# HT66F0185_NightLED_V4_0.net
KiCad netlist of a schematic drawn in Altium Designer
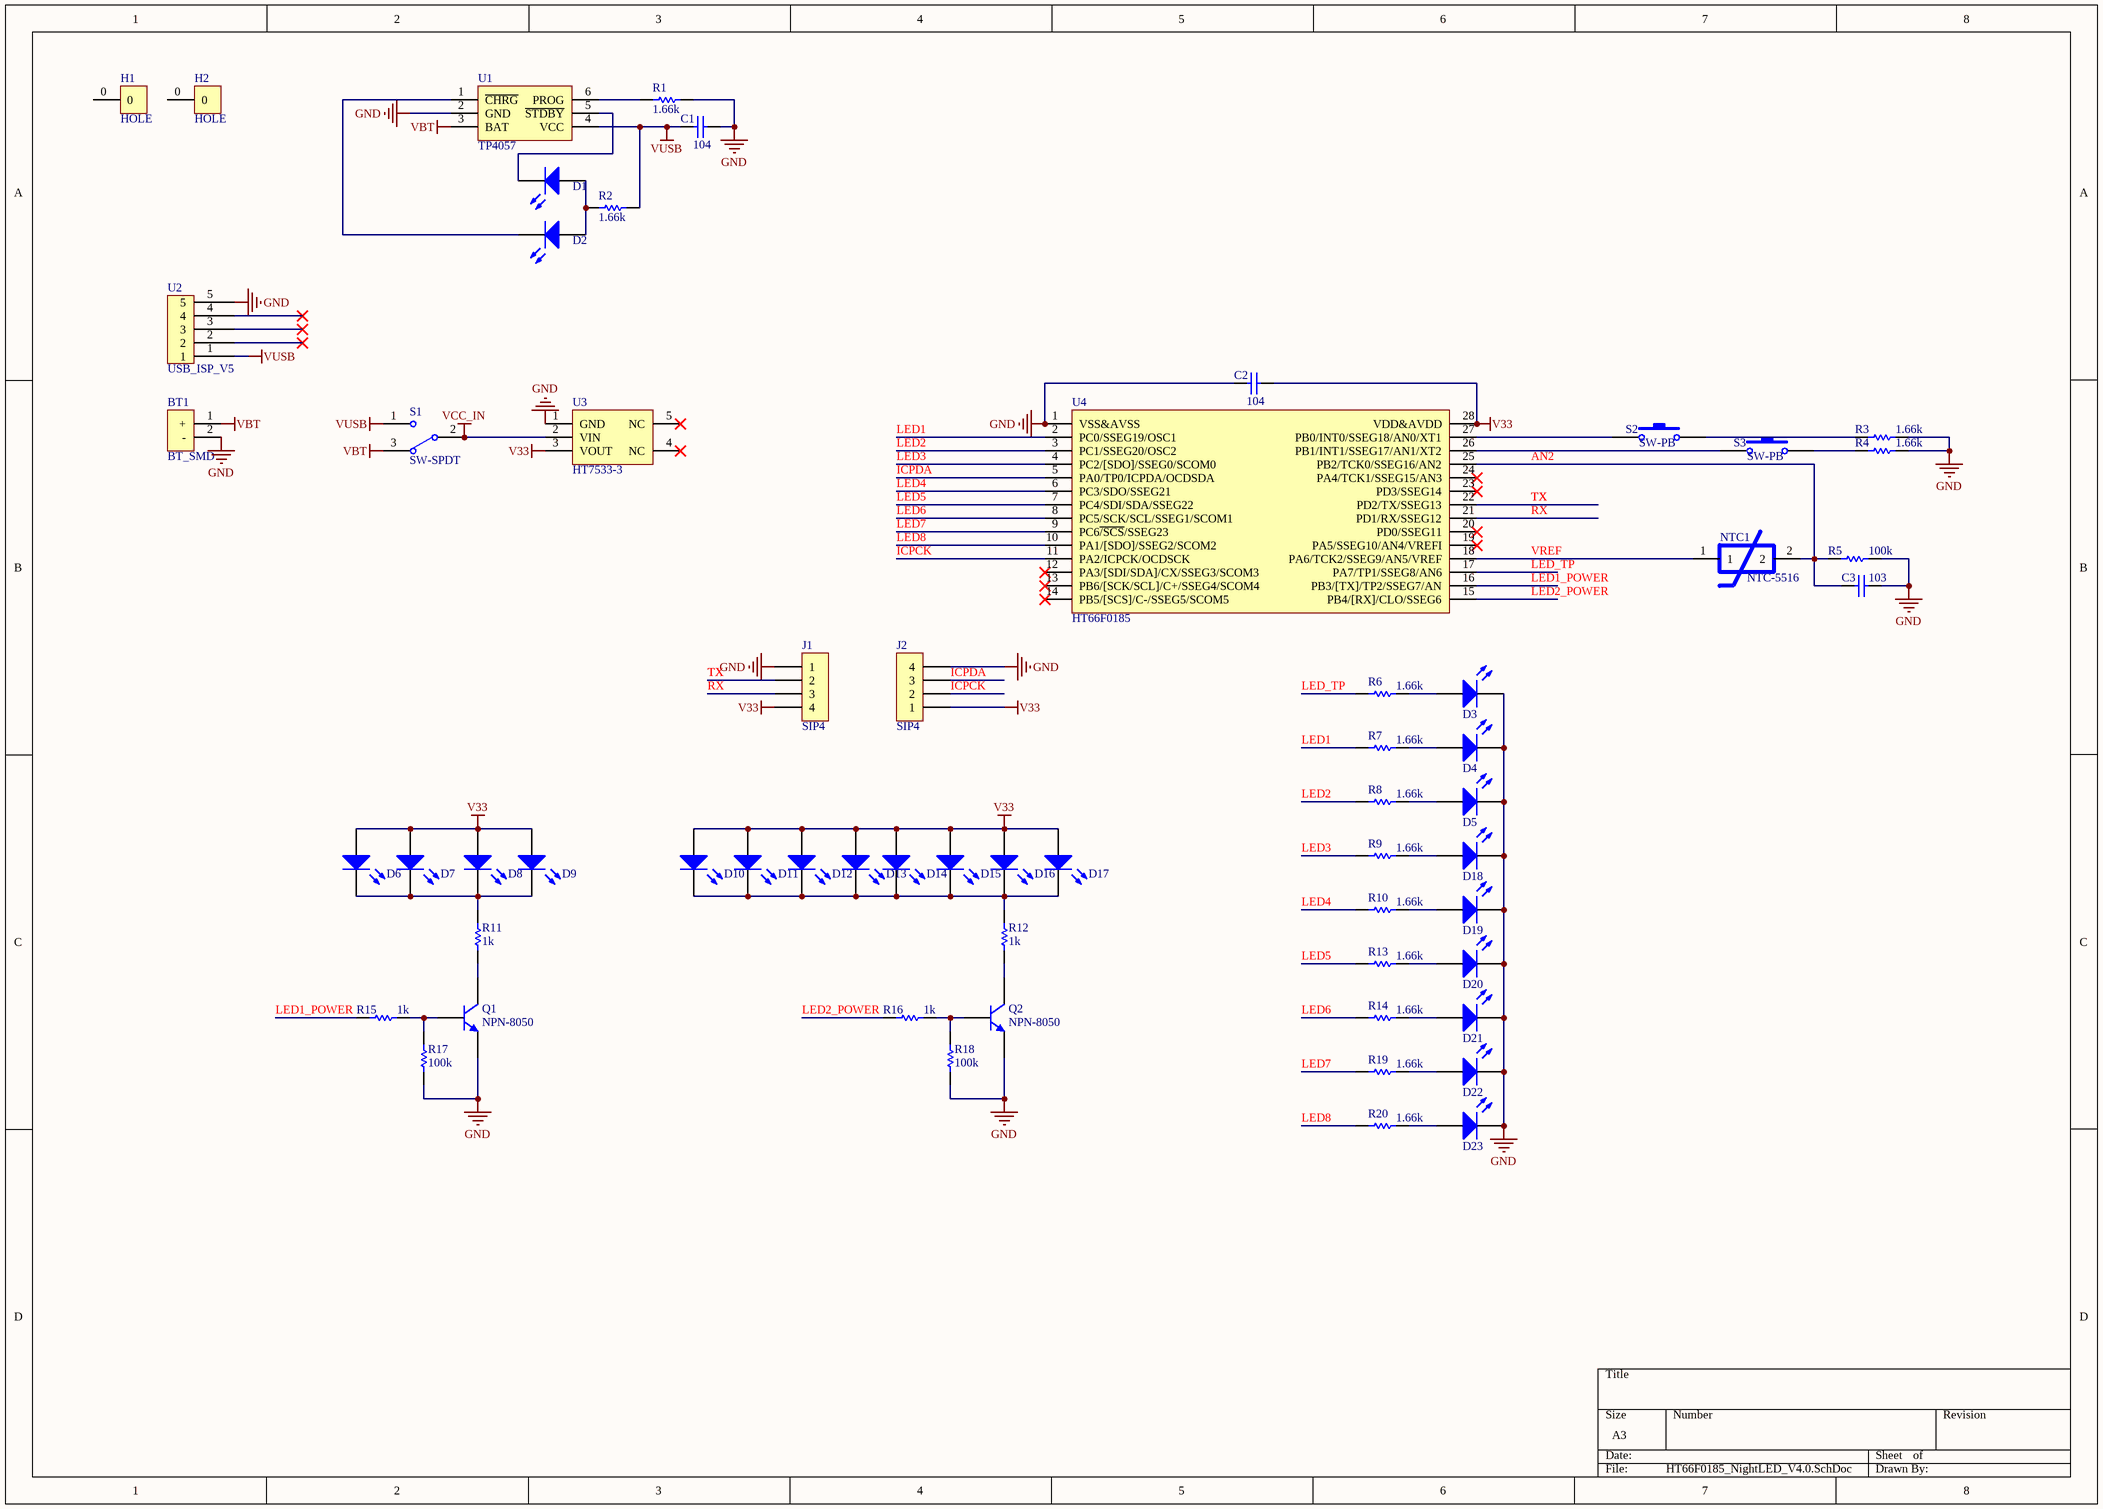
[diagram p0: HT66F0185_NightLED_V4.0.SchDoc]

(export (version "E")
  (design (tool "Eeschema 10.0.6"))
  (components
    (comp (ref "BT1")
      (value "BT_SMD")
      (footprint "PIN_2")
      (libsource (lib "HT66F0185_NightLED") (part "BT_SMD"))
    )
    (comp (ref "C1")
      (value "104")
      (footprint "C_0603")
      (description "Capacitor")
      (fields (field (name "Comment") "Cap") (field (name "PUBLISHER") "Altium Limited"))
      (libsource (lib "Miscellaneous Devices") (part "Cap"))
    )
    (comp (ref "C2")
      (value "104")
      (footprint "C_0603")
      (description "Capacitor")
      (fields (field (name "Comment") "Cap") (field (name "PUBLISHER") "Altium Limited"))
      (libsource (lib "Miscellaneous Devices") (part "Cap"))
    )
    (comp (ref "C3")
      (value "103")
      (footprint "C_0603")
      (description "Capacitor")
      (fields (field (name "Comment") "Cap") (field (name "PUBLISHER") "Altium Limited"))
      (libsource (lib "Miscellaneous Devices") (part "Cap"))
    )
    (comp (ref "D1")
      (value "LED0")
      (footprint "LED_0805(Y)")
      (description "Typical INFRARED GaAs LED")
      (fields (field (name "PUBLISHER") "Altium Limited"))
      (libsource (lib "zhiwu_Project") (part "LED0"))
    )
    (comp (ref "D2")
      (value "LED0")
      (footprint "LED_0805(Y)")
      (description "Typical INFRARED GaAs LED")
      (fields (field (name "PUBLISHER") "Altium Limited"))
      (libsource (lib "zhiwu_Project") (part "LED0"))
    )
    (comp (ref "D3")
      (value "LED0")
      (footprint "LED_0805(Y)")
      (description "Typical INFRARED GaAs LED")
      (fields (field (name "PUBLISHER") "Altium Limited"))
      (libsource (lib "zhiwu_Project") (part "LED0"))
    )
    (comp (ref "D4")
      (value "LED0")
      (footprint "LED_0805(Y)")
      (description "Typical INFRARED GaAs LED")
      (fields (field (name "PUBLISHER") "Altium Limited"))
      (libsource (lib "zhiwu_Project") (part "LED0"))
    )
    (comp (ref "D5")
      (value "LED0")
      (footprint "LED_0805(Y)")
      (description "Typical INFRARED GaAs LED")
      (fields (field (name "PUBLISHER") "Altium Limited"))
      (libsource (lib "zhiwu_Project") (part "LED0"))
    )
    (comp (ref "D6")
      (value "LED0")
      (footprint "LED_0805(Y)")
      (description "Typical INFRARED GaAs LED")
      (fields (field (name "PUBLISHER") "Altium Limited"))
      (libsource (lib "zhiwu_Project") (part "LED0"))
    )
    (comp (ref "D7")
      (value "LED0")
      (footprint "LED_0805(Y)")
      (description "Typical INFRARED GaAs LED")
      (fields (field (name "PUBLISHER") "Altium Limited"))
      (libsource (lib "zhiwu_Project") (part "LED0"))
    )
    (comp (ref "D8")
      (value "LED0")
      (footprint "LED_0805(Y)")
      (description "Typical INFRARED GaAs LED")
      (fields (field (name "PUBLISHER") "Altium Limited"))
      (libsource (lib "zhiwu_Project") (part "LED0"))
    )
    (comp (ref "D9")
      (value "LED0")
      (footprint "LED_0805(Y)")
      (description "Typical INFRARED GaAs LED")
      (fields (field (name "PUBLISHER") "Altium Limited"))
      (libsource (lib "zhiwu_Project") (part "LED0"))
    )
    (comp (ref "D10")
      (value "LED0")
      (footprint "LED_0805(Y)")
      (description "Typical INFRARED GaAs LED")
      (fields (field (name "PUBLISHER") "Altium Limited"))
      (libsource (lib "zhiwu_Project") (part "LED0"))
    )
    (comp (ref "D11")
      (value "LED0")
      (footprint "LED_0805(Y)")
      (description "Typical INFRARED GaAs LED")
      (fields (field (name "PUBLISHER") "Altium Limited"))
      (libsource (lib "zhiwu_Project") (part "LED0"))
    )
    (comp (ref "D12")
      (value "LED0")
      (footprint "LED_0805(Y)")
      (description "Typical INFRARED GaAs LED")
      (fields (field (name "PUBLISHER") "Altium Limited"))
      (libsource (lib "zhiwu_Project") (part "LED0"))
    )
    (comp (ref "D13")
      (value "LED0")
      (footprint "LED_0805(Y)")
      (description "Typical INFRARED GaAs LED")
      (fields (field (name "PUBLISHER") "Altium Limited"))
      (libsource (lib "zhiwu_Project") (part "LED0"))
    )
    (comp (ref "D14")
      (value "LED0")
      (footprint "LED_0805(Y)")
      (description "Typical INFRARED GaAs LED")
      (fields (field (name "PUBLISHER") "Altium Limited"))
      (libsource (lib "zhiwu_Project") (part "LED0"))
    )
    (comp (ref "D15")
      (value "LED0")
      (footprint "LED_0805(Y)")
      (description "Typical INFRARED GaAs LED")
      (fields (field (name "PUBLISHER") "Altium Limited"))
      (libsource (lib "zhiwu_Project") (part "LED0"))
    )
    (comp (ref "D16")
      (value "LED0")
      (footprint "LED_0805(Y)")
      (description "Typical INFRARED GaAs LED")
      (fields (field (name "PUBLISHER") "Altium Limited"))
      (libsource (lib "zhiwu_Project") (part "LED0"))
    )
    (comp (ref "D17")
      (value "LED0")
      (footprint "LED_0805(Y)")
      (description "Typical INFRARED GaAs LED")
      (fields (field (name "PUBLISHER") "Altium Limited"))
      (libsource (lib "zhiwu_Project") (part "LED0"))
    )
    (comp (ref "D18")
      (value "LED0")
      (footprint "LED_0805(Y)")
      (description "Typical INFRARED GaAs LED")
      (fields (field (name "PUBLISHER") "Altium Limited"))
      (libsource (lib "zhiwu_Project") (part "LED0"))
    )
    (comp (ref "D19")
      (value "LED0")
      (footprint "LED_0805(Y)")
      (description "Typical INFRARED GaAs LED")
      (fields (field (name "PUBLISHER") "Altium Limited"))
      (libsource (lib "zhiwu_Project") (part "LED0"))
    )
    (comp (ref "D20")
      (value "LED0")
      (footprint "LED_0805(Y)")
      (description "Typical INFRARED GaAs LED")
      (fields (field (name "PUBLISHER") "Altium Limited"))
      (libsource (lib "zhiwu_Project") (part "LED0"))
    )
    (comp (ref "D21")
      (value "LED0")
      (footprint "LED_0805(Y)")
      (description "Typical INFRARED GaAs LED")
      (fields (field (name "PUBLISHER") "Altium Limited"))
      (libsource (lib "zhiwu_Project") (part "LED0"))
    )
    (comp (ref "D22")
      (value "LED0")
      (footprint "LED_0805(Y)")
      (description "Typical INFRARED GaAs LED")
      (fields (field (name "PUBLISHER") "Altium Limited"))
      (libsource (lib "zhiwu_Project") (part "LED0"))
    )
    (comp (ref "D23")
      (value "LED0")
      (footprint "LED_0805(Y)")
      (description "Typical INFRARED GaAs LED")
      (fields (field (name "PUBLISHER") "Altium Limited"))
      (libsource (lib "zhiwu_Project") (part "LED0"))
    )
    (comp (ref "H1")
      (value "HOLE")
      (footprint "Screw Hole_NightLED_V4.0")
      (libsource (lib "HT68F001_LED") (part "HOLE"))
    )
    (comp (ref "H2")
      (value "HOLE")
      (footprint "Screw Hole_NightLED_V4.0")
      (libsource (lib "HT68F001_LED") (part "HOLE"))
    )
    (comp (ref "J1")
      (value "SIP4")
      (footprint "PIN_4(SMD) - duplicate")
      (description "jointbar")
      (libsource (lib "接口与插座") (part "SIP4"))
    )
    (comp (ref "J2")
      (value "SIP4")
      (footprint "PIN_4(SMD) - duplicate")
      (description "jointbar")
      (libsource (lib "") (part "SIP4_1"))
    )
    (comp (ref "NTC1")
      (value "NTC-5516")
      (footprint "PIN_2")
      (description "NTC")
      (libsource (lib "HT66F0185_NightLED") (part "NTC"))
    )
    (comp (ref "Q1")
      (value "NPN-8050")
      (footprint "SOT_23_3")
      (description "NPN Bipolar Transistor")
      (fields (field (name "PUBLISHER") "Altium Limited"))
      (libsource (lib "Miscellaneous Devices") (part "NPN"))
    )
    (comp (ref "Q2")
      (value "NPN-8050")
      (footprint "SOT_23_3")
      (description "NPN Bipolar Transistor")
      (fields (field (name "PUBLISHER") "Altium Limited"))
      (libsource (lib "Miscellaneous Devices") (part "NPN"))
    )
    (comp (ref "R1")
      (value "1.66k")
      (footprint "R_0603")
      (description "Resistor")
      (fields (field (name "Comment") "Res1") (field (name "PUBLISHER") "Altium Limited"))
      (libsource (lib "Miscellaneous Devices") (part "Res1"))
    )
    (comp (ref "R2")
      (value "1.66k")
      (footprint "R_0603")
      (description "Resistor")
      (fields (field (name "Comment") "Res1") (field (name "PUBLISHER") "Altium Limited"))
      (libsource (lib "Miscellaneous Devices") (part "Res1"))
    )
    (comp (ref "R3")
      (value "1.66k")
      (footprint "R_0603")
      (description "Resistor")
      (fields (field (name "Comment") "Res1") (field (name "PUBLISHER") "Altium Limited"))
      (libsource (lib "Miscellaneous Devices") (part "Res1"))
    )
    (comp (ref "R4")
      (value "1.66k")
      (footprint "R_0603")
      (description "Resistor")
      (fields (field (name "Comment") "Res1") (field (name "PUBLISHER") "Altium Limited"))
      (libsource (lib "Miscellaneous Devices") (part "Res1"))
    )
    (comp (ref "R5")
      (value "100k")
      (footprint "R_0603")
      (description "Resistor")
      (fields (field (name "Comment") "Res1") (field (name "PUBLISHER") "Altium Limited"))
      (libsource (lib "Miscellaneous Devices") (part "Res1"))
    )
    (comp (ref "R6")
      (value "1.66k")
      (footprint "R_0603")
      (description "Resistor")
      (fields (field (name "Comment") "Res1") (field (name "PUBLISHER") "Altium Limited"))
      (libsource (lib "Miscellaneous Devices") (part "Res1"))
    )
    (comp (ref "R7")
      (value "1.66k")
      (footprint "R_0603")
      (description "Resistor")
      (fields (field (name "Comment") "Res1") (field (name "PUBLISHER") "Altium Limited"))
      (libsource (lib "Miscellaneous Devices") (part "Res1"))
    )
    (comp (ref "R8")
      (value "1.66k")
      (footprint "R_0603")
      (description "Resistor")
      (fields (field (name "Comment") "Res1") (field (name "PUBLISHER") "Altium Limited"))
      (libsource (lib "Miscellaneous Devices") (part "Res1"))
    )
    (comp (ref "R9")
      (value "1.66k")
      (footprint "R_0603")
      (description "Resistor")
      (fields (field (name "Comment") "Res1") (field (name "PUBLISHER") "Altium Limited"))
      (libsource (lib "Miscellaneous Devices") (part "Res1"))
    )
    (comp (ref "R10")
      (value "1.66k")
      (footprint "R_0603")
      (description "Resistor")
      (fields (field (name "Comment") "Res1") (field (name "PUBLISHER") "Altium Limited"))
      (libsource (lib "Miscellaneous Devices") (part "Res1"))
    )
    (comp (ref "R11")
      (value "1k")
      (footprint "R_0603")
      (description "Resistor")
      (fields (field (name "Comment") "Res1") (field (name "PUBLISHER") "Altium Limited"))
      (libsource (lib "Miscellaneous Devices") (part "Res1"))
    )
    (comp (ref "R12")
      (value "1k")
      (footprint "R_0603")
      (description "Resistor")
      (fields (field (name "Comment") "Res1") (field (name "PUBLISHER") "Altium Limited"))
      (libsource (lib "Miscellaneous Devices") (part "Res1"))
    )
    (comp (ref "R13")
      (value "1.66k")
      (footprint "R_0603")
      (description "Resistor")
      (fields (field (name "Comment") "Res1") (field (name "PUBLISHER") "Altium Limited"))
      (libsource (lib "Miscellaneous Devices") (part "Res1"))
    )
    (comp (ref "R14")
      (value "1.66k")
      (footprint "R_0603")
      (description "Resistor")
      (fields (field (name "Comment") "Res1") (field (name "PUBLISHER") "Altium Limited"))
      (libsource (lib "Miscellaneous Devices") (part "Res1"))
    )
    (comp (ref "R15")
      (value "1k")
      (footprint "R_0603")
      (description "Resistor")
      (fields (field (name "Comment") "Res1") (field (name "PUBLISHER") "Altium Limited"))
      (libsource (lib "Miscellaneous Devices") (part "Res1"))
    )
    (comp (ref "R16")
      (value "1k")
      (footprint "R_0603")
      (description "Resistor")
      (fields (field (name "Comment") "Res1") (field (name "PUBLISHER") "Altium Limited"))
      (libsource (lib "Miscellaneous Devices") (part "Res1"))
    )
    (comp (ref "R17")
      (value "100k")
      (footprint "R_0603")
      (description "Resistor")
      (fields (field (name "Comment") "Res1") (field (name "PUBLISHER") "Altium Limited"))
      (libsource (lib "Miscellaneous Devices") (part "Res1"))
    )
    (comp (ref "R18")
      (value "100k")
      (footprint "R_0603")
      (description "Resistor")
      (fields (field (name "Comment") "Res1") (field (name "PUBLISHER") "Altium Limited"))
      (libsource (lib "Miscellaneous Devices") (part "Res1"))
    )
    (comp (ref "R19")
      (value "1.66k")
      (footprint "R_0603")
      (description "Resistor")
      (fields (field (name "Comment") "Res1") (field (name "PUBLISHER") "Altium Limited"))
      (libsource (lib "Miscellaneous Devices") (part "Res1"))
    )
    (comp (ref "R20")
      (value "1.66k")
      (footprint "R_0603")
      (description "Resistor")
      (fields (field (name "Comment") "Res1") (field (name "PUBLISHER") "Altium Limited"))
      (libsource (lib "Miscellaneous Devices") (part "Res1"))
    )
    (comp (ref "S1")
      (value "SW-SPDT")
      (footprint "SW-SPDT")
      (description "SPDT Subminiature Toggle Switch, Right Angle Mounting, Vertical Actuation")
      (fields (field (name "PUBLISHER") "Altium Limited"))
      (libsource (lib "Miscellaneous Devices") (part "SW-SPDT"))
    )
    (comp (ref "S2")
      (value "SW-PB")
      (footprint "micro button_4_SMD")
      (description "Switch")
      (fields (field (name "PUBLISHER") "Altium Limited"))
      (libsource (lib "Miscellaneous Devices") (part "SW-PB"))
    )
    (comp (ref "S3")
      (value "SW-PB")
      (footprint "micro button_2_SMD")
      (description "Switch")
      (fields (field (name "PUBLISHER") "Altium Limited"))
      (libsource (lib "Miscellaneous Devices") (part "SW-PB"))
    )
    (comp (ref "U1")
      (value "TP4057")
      (footprint "SOT_23_6")
      (libsource (lib "HT66F0185_NightLED") (part "TP4057"))
    )
    (comp (ref "U2")
      (value "USB_ISP_V5")
      (footprint "MicroUSB")
      (description "USB")
      (libsource (lib "zhiwu_Project") (part "JP5"))
    )
    (comp (ref "U3")
      (value "HT7533-3")
      (footprint "SOT_23_5")
      (libsource (lib "HT66F0185_NightLED") (part "HT7533-3"))
    )
    (comp (ref "U4")
      (value "HT66F0185")
      (footprint "SSOP_28")
      (libsource (lib "HT66F0185_NightLED") (part "HT66F0185"))
    )
  )
  (nets
    (net (code "1") (name "/AN2") (class "Default")
      (node (ref "C3") (pin "2") (pinfunction "2_2") (pintype "passive"))
      (node (ref "NTC1") (pin "2") (pinfunction "2_2") (pintype "passive"))
      (node (ref "R5") (pin "2") (pinfunction "2_2") (pintype "passive"))
      (node (ref "U4") (pin "25") (pinfunction "PB2/TCK0/SSEG16/AN2_25") (pintype "passive"))
    )
    (net (code "2") (name "/ICPCK") (class "Default")
      (node (ref "J2") (pin "2") (pinfunction "2_2") (pintype "passive"))
      (node (ref "U4") (pin "11") (pinfunction "PA2/ICPCK/OCDSCK_11") (pintype "passive"))
    )
    (net (code "3") (name "/ICPDA") (class "Default")
      (node (ref "J2") (pin "3") (pinfunction "3_3") (pintype "passive"))
      (node (ref "U4") (pin "5") (pinfunction "PA0/TP0/ICPDA/OCDSDA_5") (pintype "passive"))
    )
    (net (code "4") (name "/LED1") (class "Default")
      (node (ref "R7") (pin "2") (pinfunction "2_2") (pintype "passive"))
      (node (ref "U4") (pin "2") (pinfunction "PC0/SSEG19/OSC1_2") (pintype "passive"))
    )
    (net (code "5") (name "/LED1_POWER") (class "Default")
      (node (ref "R15") (pin "2") (pinfunction "2_2") (pintype "passive"))
      (node (ref "U4") (pin "16") (pinfunction "PB3/[TX]/TP2/SSEG7/AN_16") (pintype "passive"))
    )
    (net (code "6") (name "/LED2") (class "Default")
      (node (ref "R8") (pin "2") (pinfunction "2_2") (pintype "passive"))
      (node (ref "U4") (pin "3") (pinfunction "PC1/SSEG20/OSC2_3") (pintype "passive"))
    )
    (net (code "7") (name "/LED2_POWER") (class "Default")
      (node (ref "R16") (pin "2") (pinfunction "2_2") (pintype "passive"))
      (node (ref "U4") (pin "15") (pinfunction "PB4/[RX]/CLO/SSEG6_15") (pintype "passive"))
    )
    (net (code "8") (name "/LED3") (class "Default")
      (node (ref "R9") (pin "2") (pinfunction "2_2") (pintype "passive"))
      (node (ref "U4") (pin "4") (pinfunction "PC2/[SDO]/SSEG0/SCOM0_4") (pintype "passive"))
    )
    (net (code "9") (name "/LED4") (class "Default")
      (node (ref "R10") (pin "2") (pinfunction "2_2") (pintype "passive"))
      (node (ref "U4") (pin "6") (pinfunction "PC3/SDO/SSEG21_6") (pintype "passive"))
    )
    (net (code "10") (name "/LED5") (class "Default")
      (node (ref "R13") (pin "2") (pinfunction "2_2") (pintype "passive"))
      (node (ref "U4") (pin "7") (pinfunction "PC4/SDI/SDA/SSEG22_7") (pintype "passive"))
    )
    (net (code "11") (name "/LED6") (class "Default")
      (node (ref "R14") (pin "2") (pinfunction "2_2") (pintype "passive"))
      (node (ref "U4") (pin "8") (pinfunction "PC5/SCK/SCL/SSEG1/SCOM1_8") (pintype "passive"))
    )
    (net (code "12") (name "/LED7") (class "Default")
      (node (ref "R19") (pin "2") (pinfunction "2_2") (pintype "passive"))
      (node (ref "U4") (pin "9") (pinfunction "PC6~{/SCS}/SSEG23_9") (pintype "passive"))
    )
    (net (code "13") (name "/LED8") (class "Default")
      (node (ref "R20") (pin "2") (pinfunction "2_2") (pintype "passive"))
      (node (ref "U4") (pin "10") (pinfunction "PA1/[SDO]/SSEG2/SCOM2_10") (pintype "passive"))
    )
    (net (code "14") (name "/LED_TP") (class "Default")
      (node (ref "R6") (pin "2") (pinfunction "2_2") (pintype "passive"))
      (node (ref "U4") (pin "17") (pinfunction "PA7/TP1/SSEG8/AN6_17") (pintype "passive"))
    )
    (net (code "15") (name "/RX") (class "Default")
      (node (ref "J1") (pin "3") (pinfunction "3_3") (pintype "passive"))
      (node (ref "U4") (pin "21") (pinfunction "PD1/RX/SSEG12_21") (pintype "passive"))
    )
    (net (code "16") (name "/TX") (class "Default")
      (node (ref "J1") (pin "2") (pinfunction "2_2") (pintype "passive"))
      (node (ref "U4") (pin "22") (pinfunction "PD2/TX/SSEG13_22") (pintype "passive"))
    )
    (net (code "17") (name "/VREF") (class "Default")
      (node (ref "NTC1") (pin "1") (pinfunction "1_1") (pintype "passive"))
      (node (ref "U4") (pin "18") (pinfunction "PA6/TCK2/SSEG9/AN5/VREF_18") (pintype "passive"))
    )
    (net (code "18") (name "GND") (class "Default")
      (node (ref "BT1") (pin "2") (pinfunction "-_2") (pintype "passive"))
      (node (ref "C1") (pin "1") (pinfunction "1_1") (pintype "passive"))
      (node (ref "C2") (pin "2") (pinfunction "2_2") (pintype "passive"))
      (node (ref "C3") (pin "1") (pinfunction "1_1") (pintype "passive"))
      (node (ref "D18") (pin "2") (pinfunction "K_2") (pintype "passive"))
      (node (ref "D19") (pin "2") (pinfunction "K_2") (pintype "passive"))
      (node (ref "D20") (pin "2") (pinfunction "K_2") (pintype "passive"))
      (node (ref "D21") (pin "2") (pinfunction "K_2") (pintype "passive"))
      (node (ref "D22") (pin "2") (pinfunction "K_2") (pintype "passive"))
      (node (ref "D23") (pin "2") (pinfunction "K_2") (pintype "passive"))
      (node (ref "D3") (pin "2") (pinfunction "K_2") (pintype "passive"))
      (node (ref "D4") (pin "2") (pinfunction "K_2") (pintype "passive"))
      (node (ref "D5") (pin "2") (pinfunction "K_2") (pintype "passive"))
      (node (ref "J1") (pin "1") (pinfunction "1_1") (pintype "passive"))
      (node (ref "J2") (pin "4") (pinfunction "4_4") (pintype "passive"))
      (node (ref "Q1") (pin "3") (pinfunction "E_3") (pintype "passive"))
      (node (ref "Q2") (pin "3") (pinfunction "E_3") (pintype "passive"))
      (node (ref "R1") (pin "1") (pinfunction "1_1") (pintype "passive"))
      (node (ref "R17") (pin "2") (pinfunction "2_2") (pintype "passive"))
      (node (ref "R18") (pin "2") (pinfunction "2_2") (pintype "passive"))
      (node (ref "R3") (pin "1") (pinfunction "1_1") (pintype "passive"))
      (node (ref "R4") (pin "1") (pinfunction "1_1") (pintype "passive"))
      (node (ref "R5") (pin "1") (pinfunction "1_1") (pintype "passive"))
      (node (ref "U1") (pin "2") (pinfunction "GND_2") (pintype "passive"))
      (node (ref "U2") (pin "5") (pinfunction "5_5") (pintype "passive"))
      (node (ref "U3") (pin "1") (pinfunction "GND_1") (pintype "passive"))
      (node (ref "U4") (pin "1") (pinfunction "VSS&AVSS_1") (pintype "passive"))
    )
    (net (code "19") (name "Net-(D1-A)") (class "Default")
      (node (ref "D1") (pin "1") (pinfunction "A_1") (pintype "passive"))
      (node (ref "D2") (pin "1") (pinfunction "A_1") (pintype "passive"))
      (node (ref "R2") (pin "2") (pinfunction "2_2") (pintype "passive"))
    )
    (net (code "20") (name "Net-(D1-K)") (class "Default")
      (node (ref "D1") (pin "2") (pinfunction "K_2") (pintype "passive"))
      (node (ref "U1") (pin "5") (pinfunction "~{STDBY}_5") (pintype "passive"))
    )
    (net (code "21") (name "Net-(D2-K)") (class "Default")
      (node (ref "D2") (pin "2") (pinfunction "K_2") (pintype "passive"))
      (node (ref "U1") (pin "1") (pinfunction "~{CHRG}_1") (pintype "passive"))
    )
    (net (code "22") (name "Net-(D3-A)") (class "Default")
      (node (ref "D3") (pin "1") (pinfunction "A_1") (pintype "passive"))
      (node (ref "R6") (pin "1") (pinfunction "1_1") (pintype "passive"))
    )
    (net (code "23") (name "Net-(D4-A)") (class "Default")
      (node (ref "D4") (pin "1") (pinfunction "A_1") (pintype "passive"))
      (node (ref "R7") (pin "1") (pinfunction "1_1") (pintype "passive"))
    )
    (net (code "24") (name "Net-(D5-A)") (class "Default")
      (node (ref "D5") (pin "1") (pinfunction "A_1") (pintype "passive"))
      (node (ref "R8") (pin "1") (pinfunction "1_1") (pintype "passive"))
    )
    (net (code "25") (name "Net-(D6-K)") (class "Default")
      (node (ref "D6") (pin "2") (pinfunction "K_2") (pintype "passive"))
      (node (ref "D7") (pin "2") (pinfunction "K_2") (pintype "passive"))
      (node (ref "D8") (pin "2") (pinfunction "K_2") (pintype "passive"))
      (node (ref "D9") (pin "2") (pinfunction "K_2") (pintype "passive"))
      (node (ref "R11") (pin "1") (pinfunction "1_1") (pintype "passive"))
    )
    (net (code "26") (name "Net-(D10-K)") (class "Default")
      (node (ref "D10") (pin "2") (pinfunction "K_2") (pintype "passive"))
      (node (ref "D11") (pin "2") (pinfunction "K_2") (pintype "passive"))
      (node (ref "D12") (pin "2") (pinfunction "K_2") (pintype "passive"))
      (node (ref "D13") (pin "2") (pinfunction "K_2") (pintype "passive"))
      (node (ref "D14") (pin "2") (pinfunction "K_2") (pintype "passive"))
      (node (ref "D15") (pin "2") (pinfunction "K_2") (pintype "passive"))
      (node (ref "D16") (pin "2") (pinfunction "K_2") (pintype "passive"))
      (node (ref "D17") (pin "2") (pinfunction "K_2") (pintype "passive"))
      (node (ref "R12") (pin "1") (pinfunction "1_1") (pintype "passive"))
    )
    (net (code "27") (name "Net-(D18-A)") (class "Default")
      (node (ref "D18") (pin "1") (pinfunction "A_1") (pintype "passive"))
      (node (ref "R9") (pin "1") (pinfunction "1_1") (pintype "passive"))
    )
    (net (code "28") (name "Net-(D19-A)") (class "Default")
      (node (ref "D19") (pin "1") (pinfunction "A_1") (pintype "passive"))
      (node (ref "R10") (pin "1") (pinfunction "1_1") (pintype "passive"))
    )
    (net (code "29") (name "Net-(D20-A)") (class "Default")
      (node (ref "D20") (pin "1") (pinfunction "A_1") (pintype "passive"))
      (node (ref "R13") (pin "1") (pinfunction "1_1") (pintype "passive"))
    )
    (net (code "30") (name "Net-(D21-A)") (class "Default")
      (node (ref "D21") (pin "1") (pinfunction "A_1") (pintype "passive"))
      (node (ref "R14") (pin "1") (pinfunction "1_1") (pintype "passive"))
    )
    (net (code "31") (name "Net-(D22-A)") (class "Default")
      (node (ref "D22") (pin "1") (pinfunction "A_1") (pintype "passive"))
      (node (ref "R19") (pin "1") (pinfunction "1_1") (pintype "passive"))
    )
    (net (code "32") (name "Net-(D23-A)") (class "Default")
      (node (ref "D23") (pin "1") (pinfunction "A_1") (pintype "passive"))
      (node (ref "R20") (pin "1") (pinfunction "1_1") (pintype "passive"))
    )
    (net (code "33") (name "Net-(Q1-B)") (class "Default")
      (node (ref "Q1") (pin "2") (pinfunction "B_2") (pintype "passive"))
      (node (ref "R15") (pin "1") (pinfunction "1_1") (pintype "passive"))
      (node (ref "R17") (pin "1") (pinfunction "1_1") (pintype "passive"))
    )
    (net (code "34") (name "Net-(Q1-C)") (class "Default")
      (node (ref "Q1") (pin "1") (pinfunction "C_1") (pintype "passive"))
      (node (ref "R11") (pin "2") (pinfunction "2_2") (pintype "passive"))
    )
    (net (code "35") (name "Net-(Q2-B)") (class "Default")
      (node (ref "Q2") (pin "2") (pinfunction "B_2") (pintype "passive"))
      (node (ref "R16") (pin "1") (pinfunction "1_1") (pintype "passive"))
      (node (ref "R18") (pin "1") (pinfunction "1_1") (pintype "passive"))
    )
    (net (code "36") (name "Net-(Q2-C)") (class "Default")
      (node (ref "Q2") (pin "1") (pinfunction "C_1") (pintype "passive"))
      (node (ref "R12") (pin "2") (pinfunction "2_2") (pintype "passive"))
    )
    (net (code "37") (name "Net-(R3-Pad2)") (class "Default")
      (node (ref "R3") (pin "2") (pinfunction "2_2") (pintype "passive"))
      (node (ref "S2") (pin "2") (pinfunction "2_2") (pintype "passive"))
    )
    (net (code "38") (name "Net-(R4-Pad2)") (class "Default")
      (node (ref "R4") (pin "2") (pinfunction "2_2") (pintype "passive"))
      (node (ref "S3") (pin "2") (pinfunction "2_2") (pintype "passive"))
    )
    (net (code "39") (name "Net-(U1-PROG)") (class "Default")
      (node (ref "R1") (pin "2") (pinfunction "2_2") (pintype "passive"))
      (node (ref "U1") (pin "6") (pinfunction "PROG_6") (pintype "passive"))
    )
    (net (code "40") (name "Net-(U4-PB0{slash}INT0{slash}SSEG18{slash}AN0{slash}XT1)") (class "Default")
      (node (ref "S2") (pin "1") (pinfunction "1_1") (pintype "passive"))
      (node (ref "U4") (pin "27") (pinfunction "PB0/INT0/SSEG18/AN0/XT1_27") (pintype "passive"))
    )
    (net (code "41") (name "Net-(U4-PB1{slash}INT1{slash}SSEG17{slash}AN1{slash}XT2)") (class "Default")
      (node (ref "S3") (pin "1") (pinfunction "1_1") (pintype "passive"))
      (node (ref "U4") (pin "26") (pinfunction "PB1/INT1/SSEG17/AN1/XT2_26") (pintype "passive"))
    )
    (net (code "42") (name "V33") (class "Default")
      (node (ref "C2") (pin "1") (pinfunction "1_1") (pintype "passive"))
      (node (ref "D10") (pin "1") (pinfunction "A_1") (pintype "passive"))
      (node (ref "D11") (pin "1") (pinfunction "A_1") (pintype "passive"))
      (node (ref "D12") (pin "1") (pinfunction "A_1") (pintype "passive"))
      (node (ref "D13") (pin "1") (pinfunction "A_1") (pintype "passive"))
      (node (ref "D14") (pin "1") (pinfunction "A_1") (pintype "passive"))
      (node (ref "D15") (pin "1") (pinfunction "A_1") (pintype "passive"))
      (node (ref "D16") (pin "1") (pinfunction "A_1") (pintype "passive"))
      (node (ref "D17") (pin "1") (pinfunction "A_1") (pintype "passive"))
      (node (ref "D6") (pin "1") (pinfunction "A_1") (pintype "passive"))
      (node (ref "D7") (pin "1") (pinfunction "A_1") (pintype "passive"))
      (node (ref "D8") (pin "1") (pinfunction "A_1") (pintype "passive"))
      (node (ref "D9") (pin "1") (pinfunction "A_1") (pintype "passive"))
      (node (ref "J1") (pin "4") (pinfunction "4_4") (pintype "passive"))
      (node (ref "J2") (pin "1") (pinfunction "1_1") (pintype "passive"))
      (node (ref "U3") (pin "3") (pinfunction "VOUT_3") (pintype "passive"))
      (node (ref "U4") (pin "28") (pinfunction "VDD&AVDD_28") (pintype "passive"))
    )
    (net (code "43") (name "VBT") (class "Default")
      (node (ref "BT1") (pin "1") (pinfunction "+_1") (pintype "passive"))
      (node (ref "S1") (pin "3") (pinfunction "3_3") (pintype "passive"))
      (node (ref "U1") (pin "3") (pinfunction "BAT_3") (pintype "passive"))
    )
    (net (code "44") (name "VCC_IN") (class "Default")
      (node (ref "S1") (pin "2") (pinfunction "2_2") (pintype "passive"))
      (node (ref "U3") (pin "2") (pinfunction "VIN_2") (pintype "passive"))
    )
    (net (code "45") (name "VUSB") (class "Default")
      (node (ref "C1") (pin "2") (pinfunction "2_2") (pintype "passive"))
      (node (ref "R2") (pin "1") (pinfunction "1_1") (pintype "passive"))
      (node (ref "S1") (pin "1") (pinfunction "1_1") (pintype "passive"))
      (node (ref "U1") (pin "4") (pinfunction "VCC_4") (pintype "passive"))
      (node (ref "U2") (pin "1") (pinfunction "1_1") (pintype "passive"))
    )
    (net (code "46") (name "unconnected-(H1-Pad0)") (class "Default")
      (node (ref "H1") (pin "0") (pinfunction "0_0") (pintype "passive"))
    )
    (net (code "47") (name "unconnected-(H2-Pad0)") (class "Default")
      (node (ref "H2") (pin "0") (pinfunction "0_0") (pintype "passive"))
    )
    (net (code "48") (name "unconnected-(U2-Pad2)") (class "Default")
      (node (ref "U2") (pin "2") (pinfunction "2_2") (pintype "passive+no_connect"))
    )
    (net (code "49") (name "unconnected-(U2-Pad3)") (class "Default")
      (node (ref "U2") (pin "3") (pinfunction "3_3") (pintype "passive+no_connect"))
    )
    (net (code "50") (name "unconnected-(U2-Pad4)") (class "Default")
      (node (ref "U2") (pin "4") (pinfunction "4_4") (pintype "passive+no_connect"))
    )
    (net (code "51") (name "unconnected-(U3-NC-Pad4)") (class "Default")
      (node (ref "U3") (pin "4") (pinfunction "NC_4") (pintype "passive+no_connect"))
    )
    (net (code "52") (name "unconnected-(U3-NC-Pad5)") (class "Default")
      (node (ref "U3") (pin "5") (pinfunction "NC_5") (pintype "passive+no_connect"))
    )
    (net (code "53") (name "unconnected-(U4-PA3{slash}[SDI{slash}SDA]{slash}CX{slash}SSEG3{slash}SCOM3-Pad12)") (class "Default")
      (node (ref "U4") (pin "12") (pinfunction "PA3/[SDI/SDA]/CX/SSEG3/SCOM3_12") (pintype "passive+no_connect"))
    )
    (net (code "54") (name "unconnected-(U4-PA4{slash}TCK1{slash}SSEG15{slash}AN3-Pad24)") (class "Default")
      (node (ref "U4") (pin "24") (pinfunction "PA4/TCK1/SSEG15/AN3_24") (pintype "passive+no_connect"))
    )
    (net (code "55") (name "unconnected-(U4-PA5{slash}SSEG10{slash}AN4{slash}VREFI-Pad19)") (class "Default")
      (node (ref "U4") (pin "19") (pinfunction "PA5/SSEG10/AN4/VREFI_19") (pintype "passive+no_connect"))
    )
    (net (code "56") (name "unconnected-(U4-PB5{slash}[SCS]{slash}C-{slash}SSEG5{slash}SCOM5-Pad14)") (class "Default")
      (node (ref "U4") (pin "14") (pinfunction "PB5/[SCS]/C-/SSEG5/SCOM5_14") (pintype "passive+no_connect"))
    )
    (net (code "57") (name "unconnected-(U4-PB6{slash}[SCK{slash}SCL]{slash}C+{slash}SSEG4{slash}SCOM4-Pad13)") (class "Default")
      (node (ref "U4") (pin "13") (pinfunction "PB6/[SCK/SCL]/C+/SSEG4/SCOM4_13") (pintype "passive+no_connect"))
    )
    (net (code "58") (name "unconnected-(U4-PD0{slash}SSEG11-Pad20)") (class "Default")
      (node (ref "U4") (pin "20") (pinfunction "PD0/SSEG11_20") (pintype "passive+no_connect"))
    )
    (net (code "59") (name "unconnected-(U4-PD3{slash}SSEG14-Pad23)") (class "Default")
      (node (ref "U4") (pin "23") (pinfunction "PD3/SSEG14_23") (pintype "passive+no_connect"))
    )
  )
)
